# XMOD_Frontpanel.net
KiCad netlist of a schematic drawn in Altium Designer
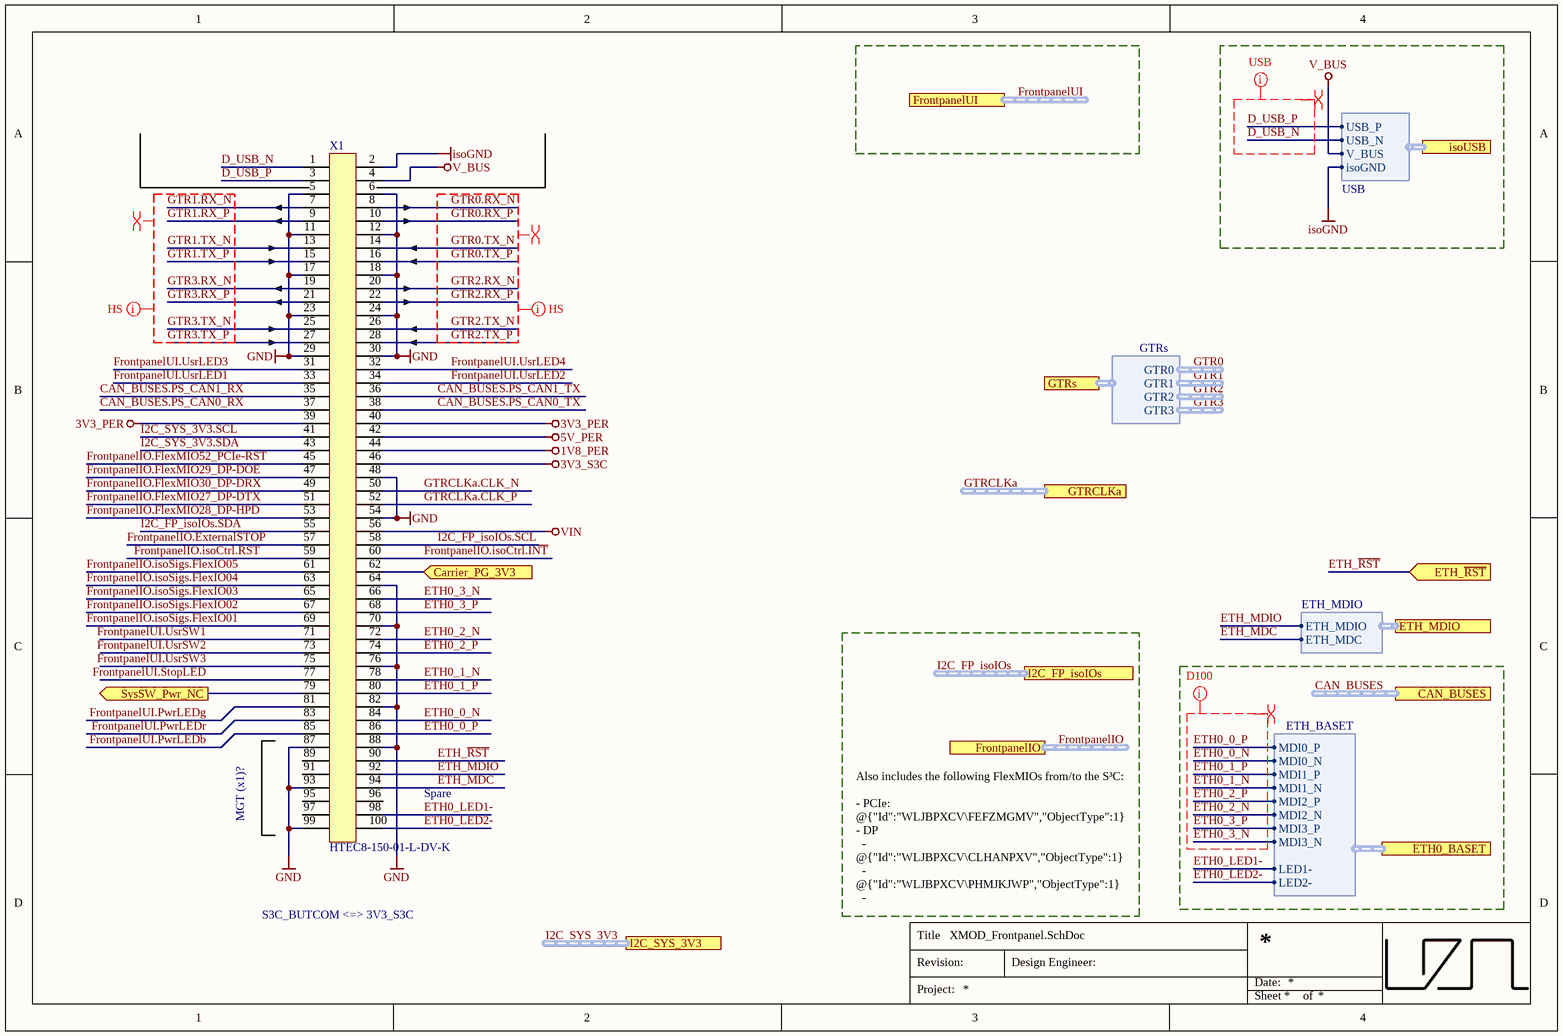
[diagram p0: XMOD_Frontpanel.SchDoc]

(export (version "E")
  (design (tool "Eeschema 10.0.6"))
  (components
    (comp (ref "X1")
      (value "HTEC8-150-01-L-DV-K")
      (footprint "HTEC8-150-XX-X-DV")
      (description "HTEC8-150-01-L-DV-K mating connector for card layout")
      (fields
        (field (name "MANUFACTURER") "SAMTEC")
        (field (name "LCSC PART NUMBER") "C20365621")
        (field (name "CREATED FROM") "MGremer")
      )
      (libsource (lib "user") (part "HTEC8-150-01-L-DV-K"))
    )
  )
  (nets
    (net (code "14") (name "/CAN_BUSES.PS_CAN0_RX") (class "Default")
      (node (ref "X1") (pin "37") (pinfunction "37_37") (pintype "passive"))
    )
    (net (code "15") (name "/CAN_BUSES.PS_CAN0_TX") (class "Default")
      (node (ref "X1") (pin "38") (pinfunction "38_38") (pintype "passive"))
    )
    (net (code "16") (name "/CAN_BUSES.PS_CAN1_RX") (class "Default")
      (node (ref "X1") (pin "35") (pinfunction "35_35") (pintype "passive"))
    )
    (net (code "17") (name "/CAN_BUSES.PS_CAN1_TX") (class "Default")
      (node (ref "X1") (pin "36") (pinfunction "36_36") (pintype "passive"))
    )
    (net (code "18") (name "/Carrier_PG_3V3") (class "Default")
      (node (ref "X1") (pin "62") (pinfunction "62_62") (pintype "passive"))
    )
    (net (code "19") (name "/D_USB_N") (class "Default")
      (node (ref "X1") (pin "1") (pinfunction "1_1") (pintype "passive"))
    )
    (net (code "20") (name "/D_USB_P") (class "Default")
      (node (ref "X1") (pin "3") (pinfunction "3_3") (pintype "passive"))
    )
    (net (code "21") (name "/ETH0_0_N") (class "Default")
      (node (ref "X1") (pin "84") (pinfunction "84_84") (pintype "passive"))
    )
    (net (code "22") (name "/ETH0_0_P") (class "Default")
      (node (ref "X1") (pin "86") (pinfunction "86_86") (pintype "passive"))
    )
    (net (code "23") (name "/ETH0_1_N") (class "Default")
      (node (ref "X1") (pin "78") (pinfunction "78_78") (pintype "passive"))
    )
    (net (code "24") (name "/ETH0_1_P") (class "Default")
      (node (ref "X1") (pin "80") (pinfunction "80_80") (pintype "passive"))
    )
    (net (code "25") (name "/ETH0_2_N") (class "Default")
      (node (ref "X1") (pin "72") (pinfunction "72_72") (pintype "passive"))
    )
    (net (code "26") (name "/ETH0_2_P") (class "Default")
      (node (ref "X1") (pin "74") (pinfunction "74_74") (pintype "passive"))
    )
    (net (code "27") (name "/ETH0_3_N") (class "Default")
      (node (ref "X1") (pin "66") (pinfunction "66_66") (pintype "passive"))
    )
    (net (code "28") (name "/ETH0_3_P") (class "Default")
      (node (ref "X1") (pin "68") (pinfunction "68_68") (pintype "passive"))
    )
    (net (code "29") (name "/ETH0_LED1-") (class "Default")
      (node (ref "X1") (pin "98") (pinfunction "98_98") (pintype "passive"))
    )
    (net (code "30") (name "/ETH0_LED2-") (class "Default")
      (node (ref "X1") (pin "100") (pinfunction "100_100") (pintype "passive"))
    )
    (net (code "31") (name "/ETH_MDC") (class "Default")
      (node (ref "X1") (pin "94") (pinfunction "94_94") (pintype "passive"))
    )
    (net (code "32") (name "/ETH_MDIO") (class "Default")
      (node (ref "X1") (pin "92") (pinfunction "92_92") (pintype "passive"))
    )
    (net (code "33") (name "/ETH_~{RST}") (class "Default")
      (node (ref "X1") (pin "90") (pinfunction "90_90") (pintype "passive"))
    )
    (net (code "34") (name "/FrontpanelIO.ExternalSTOP") (class "Default")
      (node (ref "X1") (pin "57") (pinfunction "57_57") (pintype "passive"))
    )
    (net (code "35") (name "/FrontpanelIO.FlexMIO27_DP-DTX") (class "Default")
      (node (ref "X1") (pin "51") (pinfunction "51_51") (pintype "passive"))
    )
    (net (code "36") (name "/FrontpanelIO.FlexMIO28_DP-HPD") (class "Default")
      (node (ref "X1") (pin "53") (pinfunction "53_53") (pintype "passive"))
    )
    (net (code "37") (name "/FrontpanelIO.FlexMIO29_DP-DOE") (class "Default")
      (node (ref "X1") (pin "47") (pinfunction "47_47") (pintype "passive"))
    )
    (net (code "38") (name "/FrontpanelIO.FlexMIO30_DP-DRX") (class "Default")
      (node (ref "X1") (pin "49") (pinfunction "49_49") (pintype "passive"))
    )
    (net (code "39") (name "/FrontpanelIO.FlexMIO52_PCIe-~{RST}") (class "Default")
      (node (ref "X1") (pin "45") (pinfunction "45_45") (pintype "passive"))
    )
    (net (code "40") (name "/FrontpanelIO.isoCtrl.~{INT}") (class "Default")
      (node (ref "X1") (pin "60") (pinfunction "60_60") (pintype "passive"))
    )
    (net (code "41") (name "/FrontpanelIO.isoCtrl.~{RST}") (class "Default")
      (node (ref "X1") (pin "59") (pinfunction "59_59") (pintype "passive"))
    )
    (net (code "42") (name "/FrontpanelIO.isoSigs.FlexIO01") (class "Default")
      (node (ref "X1") (pin "69") (pinfunction "69_69") (pintype "passive"))
    )
    (net (code "43") (name "/FrontpanelIO.isoSigs.FlexIO02") (class "Default")
      (node (ref "X1") (pin "67") (pinfunction "67_67") (pintype "passive"))
    )
    (net (code "44") (name "/FrontpanelIO.isoSigs.FlexIO03") (class "Default")
      (node (ref "X1") (pin "65") (pinfunction "65_65") (pintype "passive"))
    )
    (net (code "45") (name "/FrontpanelIO.isoSigs.FlexIO04") (class "Default")
      (node (ref "X1") (pin "63") (pinfunction "63_63") (pintype "passive"))
    )
    (net (code "46") (name "/FrontpanelIO.isoSigs.FlexIO05") (class "Default")
      (node (ref "X1") (pin "61") (pinfunction "61_61") (pintype "passive"))
    )
    (net (code "47") (name "/FrontpanelUI.PwrLEDb") (class "Default")
      (node (ref "X1") (pin "85") (pinfunction "85_85") (pintype "passive"))
    )
    (net (code "48") (name "/FrontpanelUI.PwrLEDg") (class "Default")
      (node (ref "X1") (pin "81") (pinfunction "81_81") (pintype "passive"))
    )
    (net (code "49") (name "/FrontpanelUI.PwrLEDr") (class "Default")
      (node (ref "X1") (pin "83") (pinfunction "83_83") (pintype "passive"))
    )
    (net (code "50") (name "/FrontpanelUI.StopLED") (class "Default")
      (node (ref "X1") (pin "77") (pinfunction "77_77") (pintype "passive"))
    )
    (net (code "51") (name "/FrontpanelUI.UsrLED1") (class "Default")
      (node (ref "X1") (pin "33") (pinfunction "33_33") (pintype "passive"))
    )
    (net (code "52") (name "/FrontpanelUI.UsrLED2") (class "Default")
      (node (ref "X1") (pin "34") (pinfunction "34_34") (pintype "passive"))
    )
    (net (code "53") (name "/FrontpanelUI.UsrLED3") (class "Default")
      (node (ref "X1") (pin "31") (pinfunction "31_31") (pintype "passive"))
    )
    (net (code "54") (name "/FrontpanelUI.UsrLED4") (class "Default")
      (node (ref "X1") (pin "32") (pinfunction "32_32") (pintype "passive"))
    )
    (net (code "55") (name "/FrontpanelUI.UsrSW1") (class "Default")
      (node (ref "X1") (pin "71") (pinfunction "71_71") (pintype "passive"))
    )
    (net (code "56") (name "/FrontpanelUI.UsrSW2") (class "Default")
      (node (ref "X1") (pin "73") (pinfunction "73_73") (pintype "passive"))
    )
    (net (code "57") (name "/FrontpanelUI.UsrSW3") (class "Default")
      (node (ref "X1") (pin "75") (pinfunction "75_75") (pintype "passive"))
    )
    (net (code "58") (name "/GTR0.RX_N") (class "Default")
      (node (ref "X1") (pin "8") (pinfunction "8_8") (pintype "passive"))
    )
    (net (code "59") (name "/GTR0.RX_P") (class "Default")
      (node (ref "X1") (pin "10") (pinfunction "10_10") (pintype "passive"))
    )
    (net (code "60") (name "/GTR0.TX_N") (class "Default")
      (node (ref "X1") (pin "14") (pinfunction "14_14") (pintype "passive"))
    )
    (net (code "61") (name "/GTR0.TX_P") (class "Default")
      (node (ref "X1") (pin "16") (pinfunction "16_16") (pintype "passive"))
    )
    (net (code "63") (name "/GTR1.RX_N") (class "Default")
      (node (ref "X1") (pin "7") (pinfunction "7_7") (pintype "passive"))
    )
    (net (code "64") (name "/GTR1.RX_P") (class "Default")
      (node (ref "X1") (pin "9") (pinfunction "9_9") (pintype "passive"))
    )
    (net (code "65") (name "/GTR1.TX_N") (class "Default")
      (node (ref "X1") (pin "13") (pinfunction "13_13") (pintype "passive"))
    )
    (net (code "66") (name "/GTR1.TX_P") (class "Default")
      (node (ref "X1") (pin "15") (pinfunction "15_15") (pintype "passive"))
    )
    (net (code "67") (name "/GTR2.RX_N") (class "Default")
      (node (ref "X1") (pin "20") (pinfunction "20_20") (pintype "passive"))
    )
    (net (code "68") (name "/GTR2.RX_P") (class "Default")
      (node (ref "X1") (pin "22") (pinfunction "22_22") (pintype "passive"))
    )
    (net (code "69") (name "/GTR2.TX_N") (class "Default")
      (node (ref "X1") (pin "26") (pinfunction "26_26") (pintype "passive"))
    )
    (net (code "70") (name "/GTR2.TX_P") (class "Default")
      (node (ref "X1") (pin "28") (pinfunction "28_28") (pintype "passive"))
    )
    (net (code "71") (name "/GTR3.RX_N") (class "Default")
      (node (ref "X1") (pin "19") (pinfunction "19_19") (pintype "passive"))
    )
    (net (code "72") (name "/GTR3.RX_P") (class "Default")
      (node (ref "X1") (pin "21") (pinfunction "21_21") (pintype "passive"))
    )
    (net (code "73") (name "/GTR3.TX_N") (class "Default")
      (node (ref "X1") (pin "25") (pinfunction "25_25") (pintype "passive"))
    )
    (net (code "74") (name "/GTR3.TX_P") (class "Default")
      (node (ref "X1") (pin "27") (pinfunction "27_27") (pintype "passive"))
    )
    (net (code "75") (name "/GTRCLKa.CLK_N") (class "Default")
      (node (ref "X1") (pin "50") (pinfunction "50_50") (pintype "passive"))
    )
    (net (code "76") (name "/GTRCLKa.CLK_P") (class "Default")
      (node (ref "X1") (pin "52") (pinfunction "52_52") (pintype "passive"))
    )
    (net (code "78") (name "/I2C_FP_isoIOs.SCL") (class "Default")
      (node (ref "X1") (pin "58") (pinfunction "58_58") (pintype "passive"))
    )
    (net (code "79") (name "/I2C_FP_isoIOs.SDA") (class "Default")
      (node (ref "X1") (pin "55") (pinfunction "55_55") (pintype "passive"))
    )
    (net (code "80") (name "/I2C_SYS_3V3.SCL") (class "Default")
      (node (ref "X1") (pin "41") (pinfunction "41_41") (pintype "passive"))
    )
    (net (code "81") (name "/I2C_SYS_3V3.SDA") (class "Default")
      (node (ref "X1") (pin "43") (pinfunction "43_43") (pintype "passive"))
    )
    (net (code "82") (name "/SysSW_Pwr_NC") (class "Default")
      (node (ref "X1") (pin "79") (pinfunction "79_79") (pintype "passive"))
    )
    (net (code "95") (name "1V8_PER") (class "Default")
      (node (ref "X1") (pin "44") (pinfunction "44_44") (pintype "passive"))
    )
    (net (code "96") (name "3V3_PER") (class "Default")
      (node (ref "X1") (pin "39") (pinfunction "39_39") (pintype "passive"))
      (node (ref "X1") (pin "40") (pinfunction "40_40") (pintype "passive"))
    )
    (net (code "97") (name "3V3_S3C") (class "Default")
      (node (ref "X1") (pin "46") (pinfunction "46_46") (pintype "passive"))
    )
    (net (code "98") (name "5V_PER") (class "Default")
      (node (ref "X1") (pin "42") (pinfunction "42_42") (pintype "passive"))
    )
    (net (code "99") (name "GND") (class "Default")
      (node (ref "X1") (pin "11") (pinfunction "11_11") (pintype "passive"))
      (node (ref "X1") (pin "12") (pinfunction "12_12") (pintype "passive"))
      (node (ref "X1") (pin "17") (pinfunction "17_17") (pintype "passive"))
      (node (ref "X1") (pin "18") (pinfunction "18_18") (pintype "passive"))
      (node (ref "X1") (pin "23") (pinfunction "23_23") (pintype "passive"))
      (node (ref "X1") (pin "24") (pinfunction "24_24") (pintype "passive"))
      (node (ref "X1") (pin "29") (pinfunction "29_29") (pintype "passive"))
      (node (ref "X1") (pin "30") (pinfunction "30_30") (pintype "passive"))
      (node (ref "X1") (pin "48") (pinfunction "48_48") (pintype "passive"))
      (node (ref "X1") (pin "5") (pinfunction "5_5") (pintype "passive"))
      (node (ref "X1") (pin "54") (pinfunction "54_54") (pintype "passive"))
      (node (ref "X1") (pin "6") (pinfunction "6_6") (pintype "passive"))
      (node (ref "X1") (pin "64") (pinfunction "64_64") (pintype "passive"))
      (node (ref "X1") (pin "70") (pinfunction "70_70") (pintype "passive"))
      (node (ref "X1") (pin "76") (pinfunction "76_76") (pintype "passive"))
      (node (ref "X1") (pin "82") (pinfunction "82_82") (pintype "passive"))
      (node (ref "X1") (pin "87") (pinfunction "87_87") (pintype "passive"))
      (node (ref "X1") (pin "88") (pinfunction "88_88") (pintype "passive"))
      (node (ref "X1") (pin "93") (pinfunction "93_93") (pintype "passive"))
      (node (ref "X1") (pin "99") (pinfunction "99_99") (pintype "passive"))
    )
    (net (code "100") (name "VIN") (class "Default")
      (node (ref "X1") (pin "56") (pinfunction "56_56") (pintype "passive"))
    )
    (net (code "101") (name "V_BUS") (class "Default")
      (node (ref "X1") (pin "4") (pinfunction "4_4") (pintype "passive"))
    )
    (net (code "102") (name "isoGND") (class "Default")
      (node (ref "X1") (pin "2") (pinfunction "2_2") (pintype "passive"))
    )
    (net (code "103") (name "unconnected-(X1-Pad89)") (class "Default")
      (node (ref "X1") (pin "89") (pinfunction "89_89") (pintype "passive"))
    )
    (net (code "104") (name "unconnected-(X1-Pad91)") (class "Default")
      (node (ref "X1") (pin "91") (pinfunction "91_91") (pintype "passive"))
    )
    (net (code "105") (name "unconnected-(X1-Pad95)") (class "Default")
      (node (ref "X1") (pin "95") (pinfunction "95_95") (pintype "passive"))
    )
    (net (code "106") (name "unconnected-(X1-Pad96)") (class "Default")
      (node (ref "X1") (pin "96") (pinfunction "96_96") (pintype "passive"))
    )
    (net (code "107") (name "unconnected-(X1-Pad97)") (class "Default")
      (node (ref "X1") (pin "97") (pinfunction "97_97") (pintype "passive"))
    )
  )
)
